# Gas_Sensor.net
KiCad netlist of a schematic drawn in EAGLE
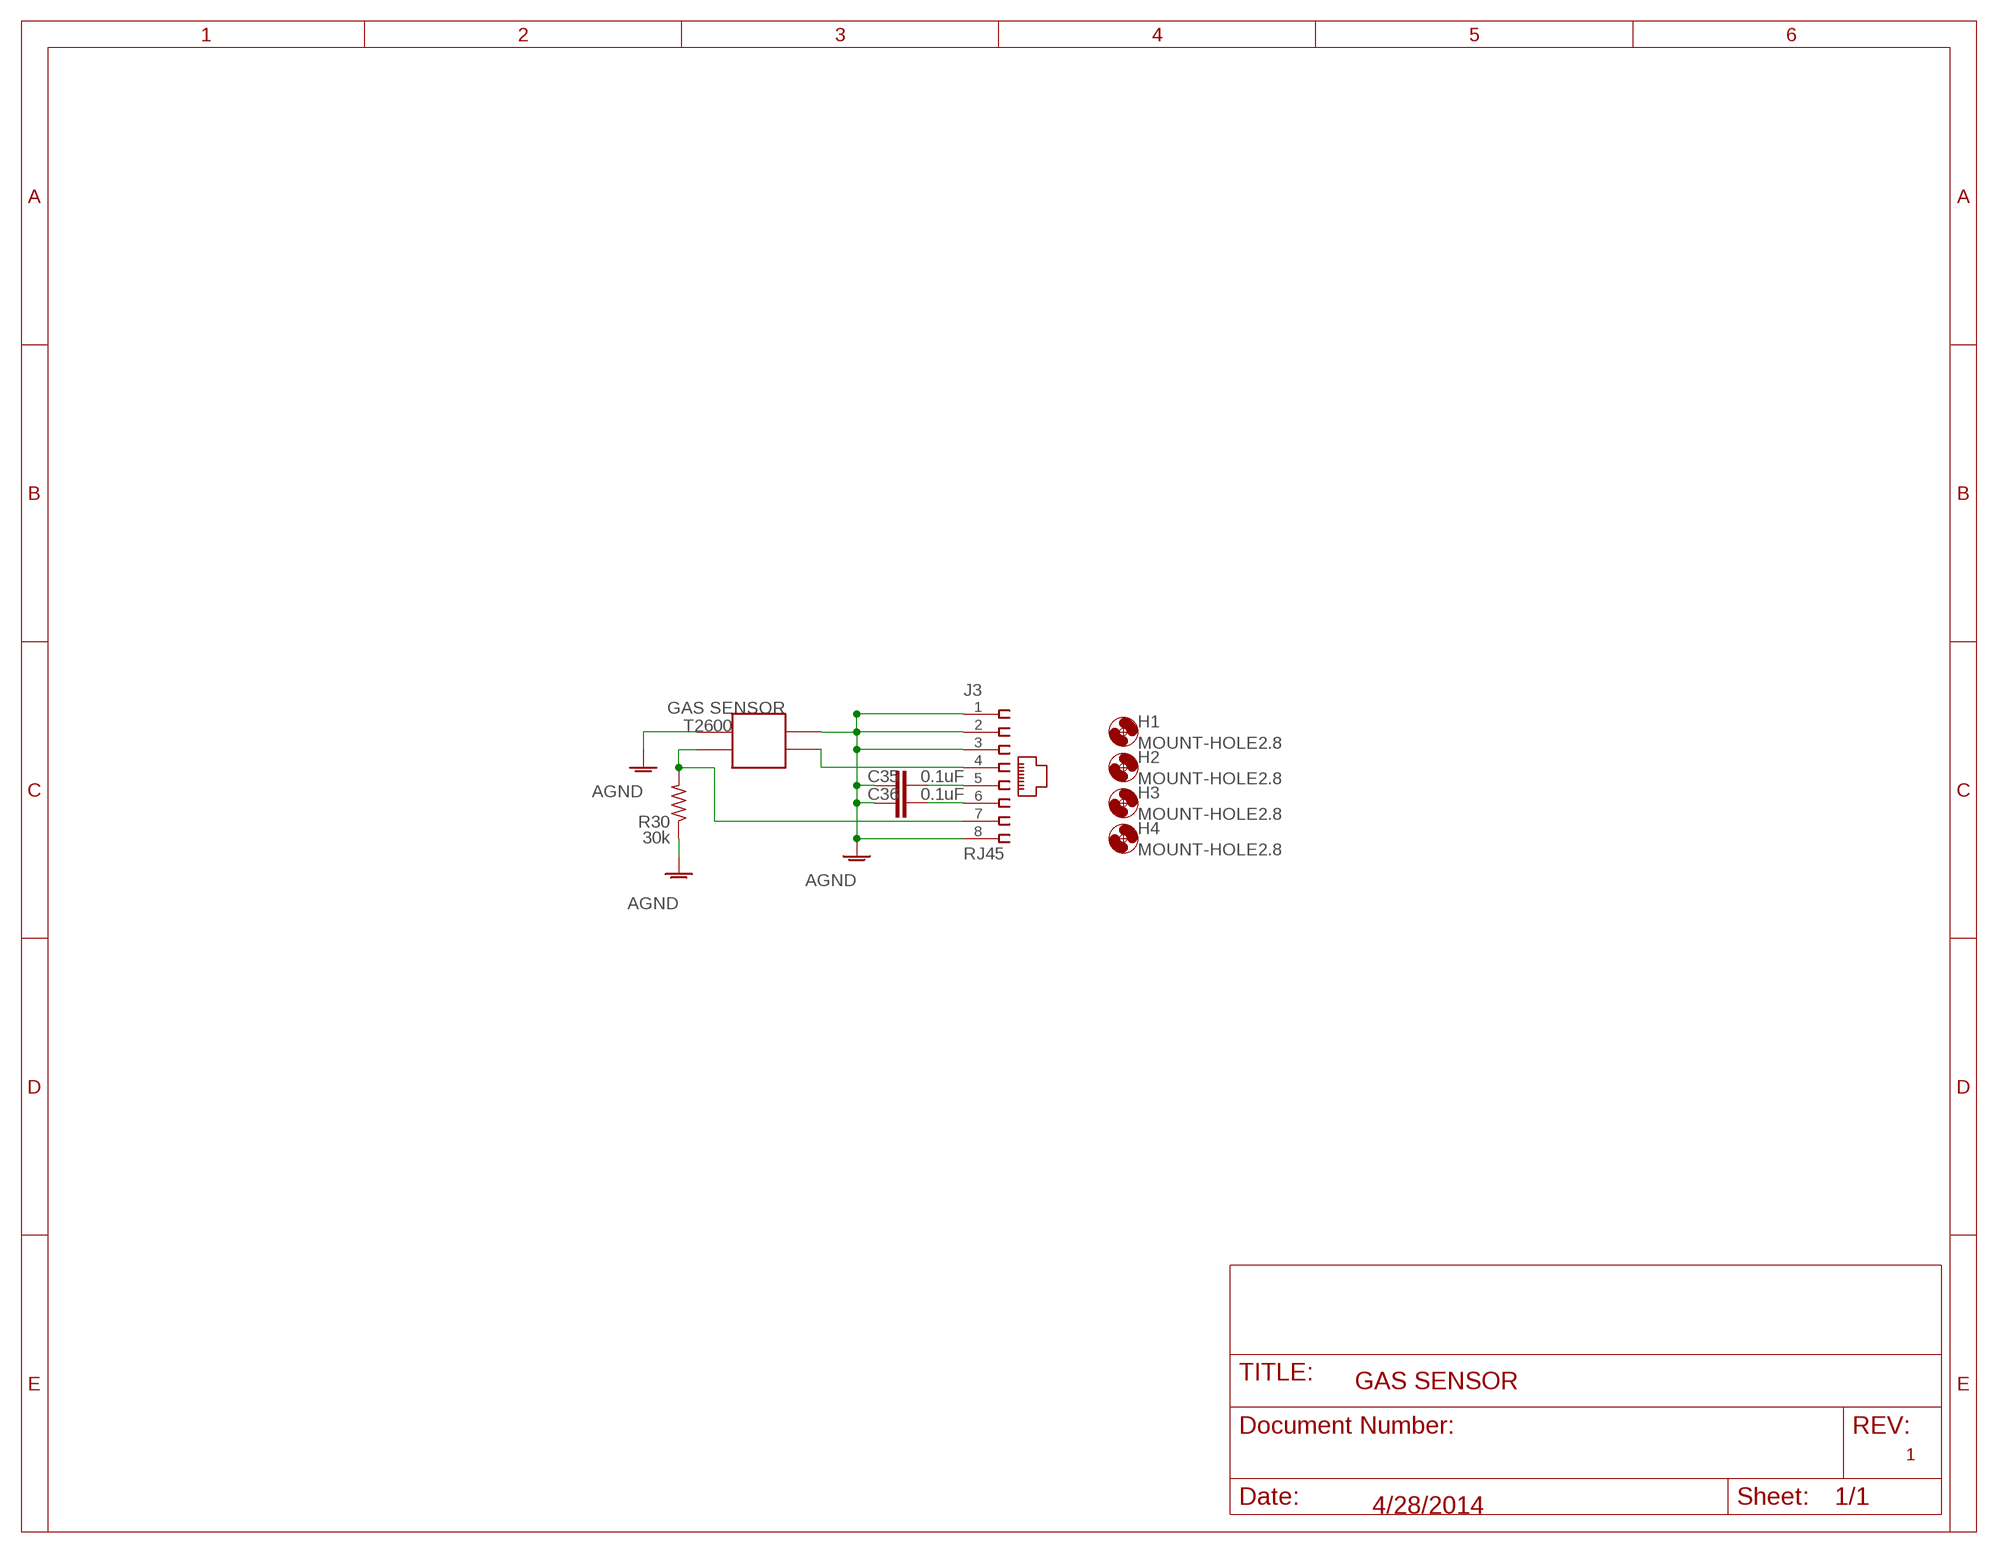
[diagram p0: schematic, sheet 1]

(export (version "E")
  (design (tool "Eeschema 10.0.6"))
  (components
    (comp (ref "C35")
      (value "0.1uF")
      (footprint "eagle-import:C0603K")
      (libsource (lib "eagle-import") (part "C-EUC0603K"))
    )
    (comp (ref "C36")
      (value "0.1uF")
      (footprint "eagle-import:C0603K")
      (libsource (lib "eagle-import") (part "C-EUC0603K"))
    )
    (comp (ref "H1")
      (value "MOUNT-HOLE2.8")
      (footprint "eagle-import:2,8")
      (libsource (lib "eagle-import") (part "MOUNT-HOLE2.8"))
    )
    (comp (ref "H2")
      (value "MOUNT-HOLE2.8")
      (footprint "eagle-import:2,8")
      (libsource (lib "eagle-import") (part "MOUNT-HOLE2.8"))
    )
    (comp (ref "H3")
      (value "MOUNT-HOLE2.8")
      (footprint "eagle-import:2,8")
      (libsource (lib "eagle-import") (part "MOUNT-HOLE2.8"))
    )
    (comp (ref "H4")
      (value "MOUNT-HOLE2.8")
      (footprint "eagle-import:2,8")
      (libsource (lib "eagle-import") (part "MOUNT-HOLE2.8"))
    )
    (comp (ref "J3")
      (value "RJ45")
      (footprint "eagle-import:555167-1")
      (libsource (lib "eagle-import") (part "555167-1"))
    )
    (comp (ref "R30")
      (value "30k")
      (footprint "eagle-import:R1206")
      (libsource (lib "eagle-import") (part "R-US_R1206"))
    )
    (comp (ref "X1")
      (value "GAS_SENSOR")
      (footprint "eagle-import:GAS_SENSOR")
      (libsource (lib "eagle-import") (part "GAS_SENSOR"))
    )
  )
  (nets
    (net (code "1") (name "AGND") (class "Default")
      (node (ref "C35") (pin "2") (pinfunction "2_2") (pintype "passive"))
      (node (ref "C36") (pin "2") (pinfunction "2_2") (pintype "passive"))
      (node (ref "J3") (pin "1") (pinfunction "1_1") (pintype "passive"))
      (node (ref "J3") (pin "2") (pinfunction "2_2") (pintype "passive"))
      (node (ref "J3") (pin "3") (pinfunction "3_3") (pintype "passive"))
      (node (ref "J3") (pin "8") (pinfunction "8_8") (pintype "passive"))
      (node (ref "R30") (pin "1") (pinfunction "1_1") (pintype "passive"))
      (node (ref "X1") (pin "P$1") (pinfunction "P$4_P$1") (pintype "bidirectional"))
      (node (ref "X1") (pin "P$2") (pinfunction "P$1_P$2") (pintype "bidirectional"))
    )
    (net (code "2") (name "Net-(C35-Pad1)") (class "Default")
      (node (ref "C35") (pin "1") (pinfunction "1_1") (pintype "passive"))
      (node (ref "J3") (pin "5") (pinfunction "5_5") (pintype "passive"))
    )
    (net (code "3") (name "Net-(C36-Pad1)") (class "Default")
      (node (ref "C36") (pin "1") (pinfunction "1_1") (pintype "passive"))
      (node (ref "J3") (pin "6") (pinfunction "6_6") (pintype "passive"))
    )
    (net (code "4") (name "Net-(J3-Pad4)") (class "Default")
      (node (ref "J3") (pin "4") (pinfunction "4_4") (pintype "passive"))
      (node (ref "X1") (pin "P$3") (pinfunction "P$3_P$3") (pintype "bidirectional"))
    )
    (net (code "5") (name "Net-(X1-P$2)") (class "Default")
      (node (ref "J3") (pin "7") (pinfunction "7_7") (pintype "passive"))
      (node (ref "R30") (pin "2") (pinfunction "2_2") (pintype "passive"))
      (node (ref "X1") (pin "P$4") (pinfunction "P$2_P$4") (pintype "bidirectional"))
    )
  )
)
